# Rocket_Controller_ver2_00.net
KiCad netlist of a schematic drawn in EAGLE
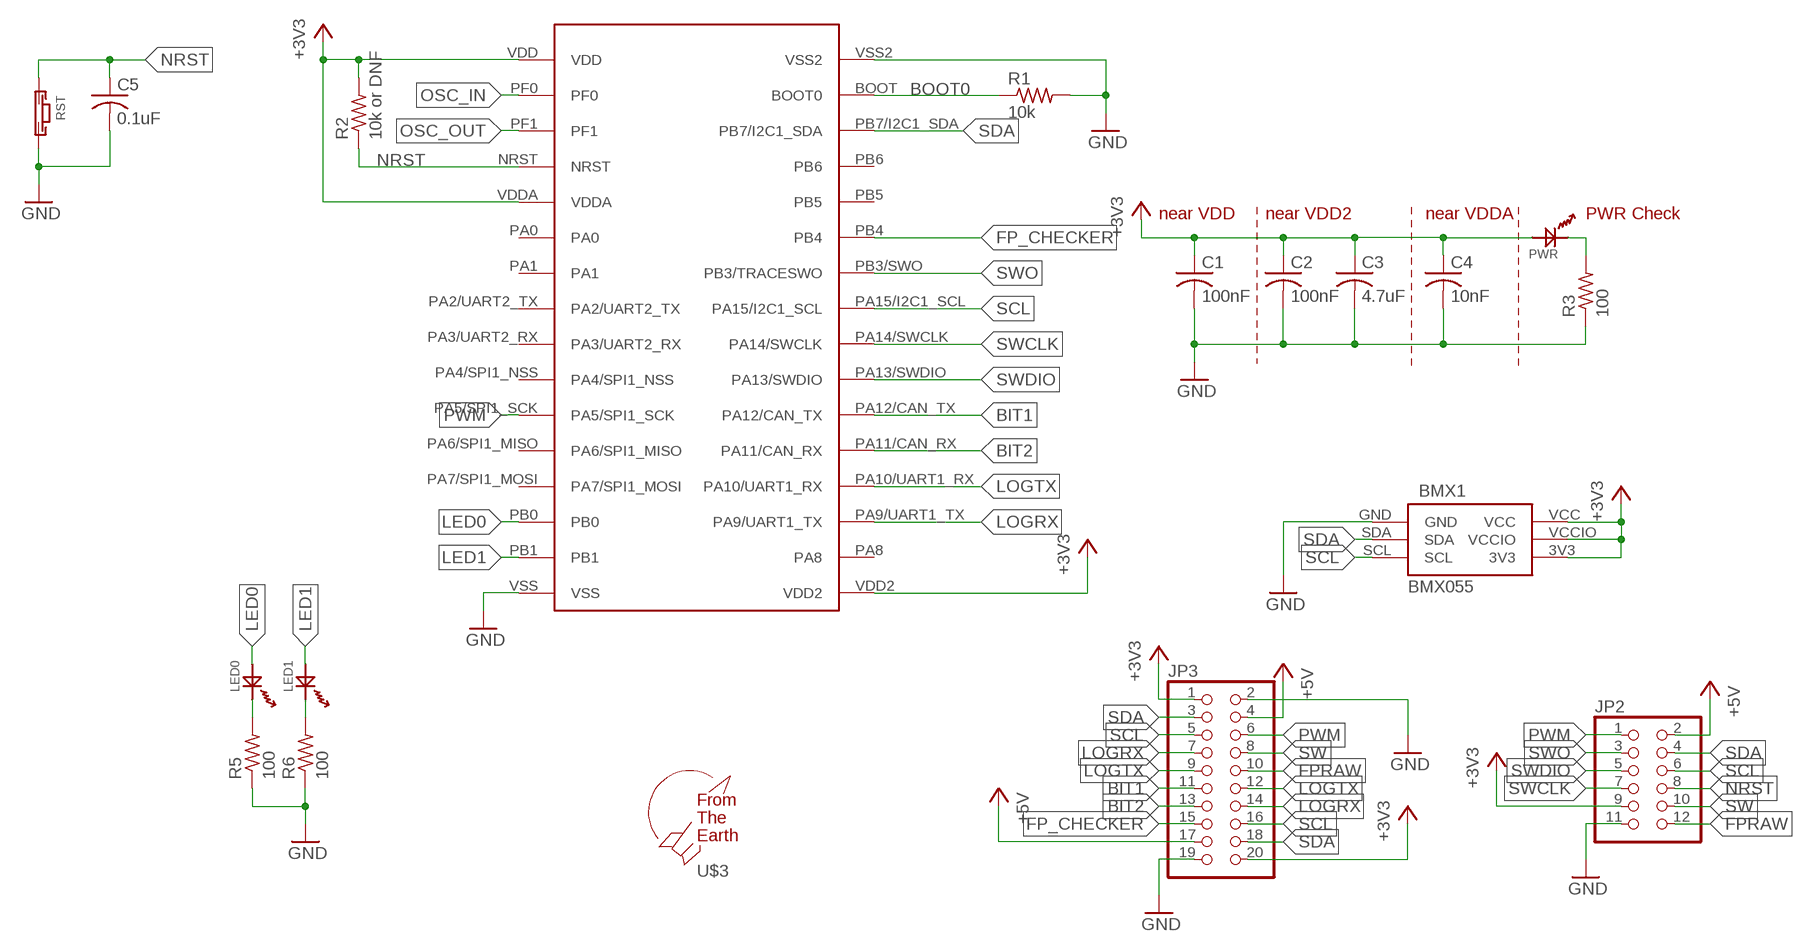
[diagram p0: schematic, sheet 1]

(export (version "E")
  (design (tool "Eeschema 10.0.6"))
  (components
    (comp (ref "BMX1")
      (value "BMX055")
      (footprint "eagle-import:BMX055")
      (libsource (lib "eagle-import") (part "BMX055"))
    )
    (comp (ref "C1")
      (value "100nF")
      (footprint "eagle-import:C1608")
      (libsource (lib "eagle-import") (part "C-USC1608"))
    )
    (comp (ref "C2")
      (value "100nF")
      (footprint "eagle-import:C1608")
      (libsource (lib "eagle-import") (part "C-USC1608"))
    )
    (comp (ref "C3")
      (value "4.7uF")
      (footprint "eagle-import:C1608")
      (libsource (lib "eagle-import") (part "C-USC1608"))
    )
    (comp (ref "C4")
      (value "10nF")
      (footprint "eagle-import:C1608")
      (libsource (lib "eagle-import") (part "C-USC1608"))
    )
    (comp (ref "C5")
      (value "0.1uF")
      (footprint "eagle-import:C1608")
      (libsource (lib "eagle-import") (part "C-USC1608"))
    )
    (comp (ref "JP2")
      (value "PINHD-2X6/90")
      (footprint "eagle-import:2X06_90")
      (libsource (lib "eagle-import") (part "PINHD-2X6/90"))
    )
    (comp (ref "JP3")
      (value "PINHD-2X10/90")
      (footprint "eagle-import:2X10_90")
      (libsource (lib "eagle-import") (part "PINHD-2X10/90"))
    )
    (comp (ref "LED0")
      (value "OSXX1608C1A")
      (footprint "eagle-import:OSXX1608C1A")
      (libsource (lib "eagle-import") (part "OSXX1608C1A"))
    )
    (comp (ref "LED1")
      (value "OSXX1608C1A")
      (footprint "eagle-import:OSXX1608C1A")
      (libsource (lib "eagle-import") (part "OSXX1608C1A"))
    )
    (comp (ref "PWR")
      (value "OSXX1608C1A")
      (footprint "eagle-import:OSXX1608C1A")
      (libsource (lib "eagle-import") (part "OSXX1608C1A"))
    )
    (comp (ref "R1")
      (value "10k")
      (footprint "eagle-import:R0603")
      (libsource (lib "eagle-import") (part "R-US_R0603"))
    )
    (comp (ref "R2")
      (value "10k or DNF")
      (footprint "eagle-import:R0603")
      (libsource (lib "eagle-import") (part "R-US_R0603"))
    )
    (comp (ref "R3")
      (value "100")
      (footprint "eagle-import:R0603")
      (libsource (lib "eagle-import") (part "R-US_R0603"))
    )
    (comp (ref "R5")
      (value "100")
      (footprint "eagle-import:R0603")
      (libsource (lib "eagle-import") (part "R-US_R0603"))
    )
    (comp (ref "R6")
      (value "100")
      (footprint "eagle-import:R0603")
      (libsource (lib "eagle-import") (part "R-US_R0603"))
    )
    (comp (ref "RST")
      (value "TVAF06-A020B-R")
      (footprint "eagle-import:TVAF06-A020B-R")
      (libsource (lib "eagle-import") (part "TVAF06-A020B-R"))
    )
    (comp (ref "U$1")
      (value "STM32F303K8")
      (footprint "eagle-import:STM32F303K8")
      (libsource (lib "eagle-import") (part "STM32F303K8"))
    )
    (comp (ref "U$3")
      (value "F.T.E.LOGO")
      (footprint "eagle-import:LOGO")
      (libsource (lib "eagle-import") (part "F.T.E.LOGO"))
    )
  )
  (nets
    (net (code "1") (name "+3V3") (class "Default")
      (node (ref "BMX1") (pin "3V3") (pinfunction "3V3_3V3") (pintype "power_in"))
      (node (ref "BMX1") (pin "VCC") (pinfunction "VCC_VCC") (pintype "power_in"))
      (node (ref "BMX1") (pin "VCCIO") (pinfunction "VCCIO_VCCIO") (pintype "power_in"))
      (node (ref "C1") (pin "1") (pinfunction "1_1") (pintype "passive"))
      (node (ref "C2") (pin "1") (pinfunction "1_1") (pintype "passive"))
      (node (ref "C3") (pin "1") (pinfunction "1_1") (pintype "passive"))
      (node (ref "C4") (pin "1") (pinfunction "1_1") (pintype "passive"))
      (node (ref "JP2") (pin "9") (pinfunction "9_9") (pintype "passive"))
      (node (ref "JP3") (pin "1") (pinfunction "1_1") (pintype "passive"))
      (node (ref "JP3") (pin "20") (pinfunction "20_20") (pintype "passive"))
      (node (ref "PWR") (pin "AN") (pinfunction "AN_AN") (pintype "bidirectional"))
      (node (ref "R2") (pin "2") (pinfunction "2_2") (pintype "passive"))
      (node (ref "U$1") (pin "VDD") (pinfunction "VDD_VDD") (pintype "power_in"))
      (node (ref "U$1") (pin "VDD2") (pinfunction "VDD2_VDD2") (pintype "power_in"))
      (node (ref "U$1") (pin "VDDA") (pinfunction "VDDA_VDDA") (pintype "power_in"))
    )
    (net (code "2") (name "+5V") (class "Default")
      (node (ref "JP2") (pin "2") (pinfunction "2_2") (pintype "passive"))
      (node (ref "JP3") (pin "17") (pinfunction "17_17") (pintype "passive"))
      (node (ref "JP3") (pin "4") (pinfunction "4_4") (pintype "passive"))
    )
    (net (code "3") (name "/BOOT0") (class "Default")
      (node (ref "R1") (pin "1") (pinfunction "1_1") (pintype "passive"))
      (node (ref "U$1") (pin "BOOT") (pinfunction "BOOT0_BOOT") (pintype "bidirectional"))
    )
    (net (code "4") (name "BIT1") (class "Default")
      (node (ref "JP3") (pin "11") (pinfunction "11_11") (pintype "passive"))
      (node (ref "U$1") (pin "PA12/CAN_TX") (pinfunction "PA12/CAN_TX_PA12/CAN_TX") (pintype "bidirectional"))
    )
    (net (code "5") (name "BIT2") (class "Default")
      (node (ref "JP3") (pin "13") (pinfunction "13_13") (pintype "passive"))
      (node (ref "U$1") (pin "PA11/CAN_RX") (pinfunction "PA11/CAN_RX_PA11/CAN_RX") (pintype "bidirectional"))
    )
    (net (code "6") (name "FPRAW") (class "Default")
      (node (ref "JP2") (pin "12") (pinfunction "12_12") (pintype "passive"))
      (node (ref "JP3") (pin "10") (pinfunction "10_10") (pintype "passive"))
    )
    (net (code "7") (name "FP_CHECKER") (class "Default")
      (node (ref "JP3") (pin "15") (pinfunction "15_15") (pintype "passive"))
      (node (ref "U$1") (pin "PB4") (pinfunction "PB4_PB4") (pintype "bidirectional"))
    )
    (net (code "8") (name "GND") (class "Default")
      (node (ref "BMX1") (pin "GND") (pinfunction "GND_GND") (pintype "power_in"))
      (node (ref "C1") (pin "2") (pinfunction "2_2") (pintype "passive"))
      (node (ref "C2") (pin "2") (pinfunction "2_2") (pintype "passive"))
      (node (ref "C3") (pin "2") (pinfunction "2_2") (pintype "passive"))
      (node (ref "C4") (pin "2") (pinfunction "2_2") (pintype "passive"))
      (node (ref "C5") (pin "2") (pinfunction "2_2") (pintype "passive"))
      (node (ref "JP2") (pin "11") (pinfunction "11_11") (pintype "passive"))
      (node (ref "JP3") (pin "19") (pinfunction "19_19") (pintype "passive"))
      (node (ref "JP3") (pin "2") (pinfunction "2_2") (pintype "passive"))
      (node (ref "R1") (pin "2") (pinfunction "2_2") (pintype "passive"))
      (node (ref "R3") (pin "1") (pinfunction "1_1") (pintype "passive"))
      (node (ref "R5") (pin "1") (pinfunction "1_1") (pintype "passive"))
      (node (ref "R6") (pin "1") (pinfunction "1_1") (pintype "passive"))
      (node (ref "RST") (pin "P$2") (pinfunction "P$2_P$2") (pintype "bidirectional"))
      (node (ref "U$1") (pin "VSS") (pinfunction "VSS_VSS") (pintype "power_in"))
      (node (ref "U$1") (pin "VSS2") (pinfunction "VSS2_VSS2") (pintype "power_in"))
    )
    (net (code "9") (name "LED0") (class "Default")
      (node (ref "LED0") (pin "AN") (pinfunction "AN_AN") (pintype "bidirectional"))
      (node (ref "U$1") (pin "PB0") (pinfunction "PB0_PB0") (pintype "bidirectional"))
    )
    (net (code "10") (name "LED1") (class "Default")
      (node (ref "LED1") (pin "AN") (pinfunction "AN_AN") (pintype "bidirectional"))
      (node (ref "U$1") (pin "PB1") (pinfunction "PB1_PB1") (pintype "bidirectional"))
    )
    (net (code "11") (name "LOGRX") (class "Default")
      (node (ref "JP3") (pin "14") (pinfunction "14_14") (pintype "passive"))
      (node (ref "JP3") (pin "7") (pinfunction "7_7") (pintype "passive"))
      (node (ref "U$1") (pin "PA9/UART1_TX") (pinfunction "PA9/UART1_TX_PA9/UART1_TX") (pintype "bidirectional"))
    )
    (net (code "12") (name "LOGTX") (class "Default")
      (node (ref "JP3") (pin "12") (pinfunction "12_12") (pintype "passive"))
      (node (ref "JP3") (pin "9") (pinfunction "9_9") (pintype "passive"))
      (node (ref "U$1") (pin "PA10/UART1_RX") (pinfunction "PA10/UART1_RX_PA10/UART1_RX") (pintype "bidirectional"))
    )
    (net (code "13") (name "NRST") (class "Default")
      (node (ref "C5") (pin "1") (pinfunction "1_1") (pintype "passive"))
      (node (ref "JP2") (pin "8") (pinfunction "8_8") (pintype "passive"))
      (node (ref "R2") (pin "1") (pinfunction "1_1") (pintype "passive"))
      (node (ref "RST") (pin "P$1") (pinfunction "P$1_P$1") (pintype "bidirectional"))
      (node (ref "U$1") (pin "NRST") (pinfunction "NRST_NRST") (pintype "bidirectional"))
    )
    (net (code "14") (name "Net-(LED0-PadCT)") (class "Default")
      (node (ref "LED0") (pin "CT") (pinfunction "CT_CT") (pintype "bidirectional"))
      (node (ref "R5") (pin "2") (pinfunction "2_2") (pintype "passive"))
    )
    (net (code "15") (name "Net-(LED1-PadCT)") (class "Default")
      (node (ref "LED1") (pin "CT") (pinfunction "CT_CT") (pintype "bidirectional"))
      (node (ref "R6") (pin "2") (pinfunction "2_2") (pintype "passive"))
    )
    (net (code "16") (name "Net-(PWR-PadCT)") (class "Default")
      (node (ref "PWR") (pin "CT") (pinfunction "CT_CT") (pintype "bidirectional"))
      (node (ref "R3") (pin "2") (pinfunction "2_2") (pintype "passive"))
    )
    (net (code "17") (name "OSC_IN") (class "Default")
      (node (ref "U$1") (pin "PF0") (pinfunction "PF0_PF0") (pintype "bidirectional"))
    )
    (net (code "18") (name "OSC_OUT") (class "Default")
      (node (ref "U$1") (pin "PF1") (pinfunction "PF1_PF1") (pintype "bidirectional"))
    )
    (net (code "19") (name "PWM") (class "Default")
      (node (ref "JP2") (pin "1") (pinfunction "1_1") (pintype "passive"))
      (node (ref "JP3") (pin "6") (pinfunction "6_6") (pintype "passive"))
      (node (ref "U$1") (pin "PA5/SPI1_SCK") (pinfunction "PA5/SPI1_SCK_PA5/SPI1_SCK") (pintype "bidirectional"))
    )
    (net (code "20") (name "SCL") (class "Default")
      (node (ref "BMX1") (pin "SCL") (pinfunction "SCL_SCL") (pintype "bidirectional"))
      (node (ref "JP2") (pin "6") (pinfunction "6_6") (pintype "passive"))
      (node (ref "JP3") (pin "16") (pinfunction "16_16") (pintype "passive"))
      (node (ref "JP3") (pin "5") (pinfunction "5_5") (pintype "passive"))
      (node (ref "U$1") (pin "PA15/I2C1_SCL") (pinfunction "PA15/I2C1_SCL_PA15/I2C1_SCL") (pintype "bidirectional"))
    )
    (net (code "21") (name "SDA") (class "Default")
      (node (ref "BMX1") (pin "SDA") (pinfunction "SDA_SDA") (pintype "bidirectional"))
      (node (ref "JP2") (pin "4") (pinfunction "4_4") (pintype "passive"))
      (node (ref "JP3") (pin "18") (pinfunction "18_18") (pintype "passive"))
      (node (ref "JP3") (pin "3") (pinfunction "3_3") (pintype "passive"))
      (node (ref "U$1") (pin "PB7/I2C1_SDA") (pinfunction "PB7/I2C1_SDA_PB7/I2C1_SDA") (pintype "bidirectional"))
    )
    (net (code "22") (name "SW") (class "Default")
      (node (ref "JP2") (pin "10") (pinfunction "10_10") (pintype "passive"))
      (node (ref "JP3") (pin "8") (pinfunction "8_8") (pintype "passive"))
    )
    (net (code "23") (name "SWCLK") (class "Default")
      (node (ref "JP2") (pin "7") (pinfunction "7_7") (pintype "passive"))
      (node (ref "U$1") (pin "PA14/SWCLK") (pinfunction "PA14/SWCLK_PA14/SWCLK") (pintype "bidirectional"))
    )
    (net (code "24") (name "SWDIO") (class "Default")
      (node (ref "JP2") (pin "5") (pinfunction "5_5") (pintype "passive"))
      (node (ref "U$1") (pin "PA13/SWDIO") (pinfunction "PA13/SWDIO_PA13/SWDIO") (pintype "bidirectional"))
    )
    (net (code "25") (name "SWO") (class "Default")
      (node (ref "JP2") (pin "3") (pinfunction "3_3") (pintype "passive"))
      (node (ref "U$1") (pin "PB3/SWO") (pinfunction "PB3/TRACESWO_PB3/SWO") (pintype "bidirectional"))
    )
    (net (code "26") (name "unconnected-(U$1-PadPA0)") (class "Default")
      (node (ref "U$1") (pin "PA0") (pinfunction "PA0_PA0") (pintype "bidirectional"))
    )
    (net (code "27") (name "unconnected-(U$1-PadPA1)") (class "Default")
      (node (ref "U$1") (pin "PA1") (pinfunction "PA1_PA1") (pintype "bidirectional"))
    )
    (net (code "28") (name "unconnected-(U$1-PadPA2{slash}UART2_TX)") (class "Default")
      (node (ref "U$1") (pin "PA2/UART2_TX") (pinfunction "PA2/UART2_TX_PA2/UART2_TX") (pintype "bidirectional"))
    )
    (net (code "29") (name "unconnected-(U$1-PadPA3{slash}UART2_RX)") (class "Default")
      (node (ref "U$1") (pin "PA3/UART2_RX") (pinfunction "PA3/UART2_RX_PA3/UART2_RX") (pintype "bidirectional"))
    )
    (net (code "30") (name "unconnected-(U$1-PadPA4{slash}SPI1_NSS)") (class "Default")
      (node (ref "U$1") (pin "PA4/SPI1_NSS") (pinfunction "PA4/SPI1_NSS_PA4/SPI1_NSS") (pintype "bidirectional"))
    )
    (net (code "31") (name "unconnected-(U$1-PadPA6{slash}SPI1_MISO)") (class "Default")
      (node (ref "U$1") (pin "PA6/SPI1_MISO") (pinfunction "PA6/SPI1_MISO_PA6/SPI1_MISO") (pintype "bidirectional"))
    )
    (net (code "32") (name "unconnected-(U$1-PadPA7{slash}SPI1_MOSI)") (class "Default")
      (node (ref "U$1") (pin "PA7/SPI1_MOSI") (pinfunction "PA7/SPI1_MOSI_PA7/SPI1_MOSI") (pintype "bidirectional"))
    )
    (net (code "33") (name "unconnected-(U$1-PadPA8)") (class "Default")
      (node (ref "U$1") (pin "PA8") (pinfunction "PA8_PA8") (pintype "bidirectional"))
    )
    (net (code "34") (name "unconnected-(U$1-PadPB5)") (class "Default")
      (node (ref "U$1") (pin "PB5") (pinfunction "PB5_PB5") (pintype "bidirectional"))
    )
    (net (code "35") (name "unconnected-(U$1-PadPB6)") (class "Default")
      (node (ref "U$1") (pin "PB6") (pinfunction "PB6_PB6") (pintype "bidirectional"))
    )
  )
)
